# fpga-enet2.net
KiCad netlist of a schematic drawn in Altium Designer
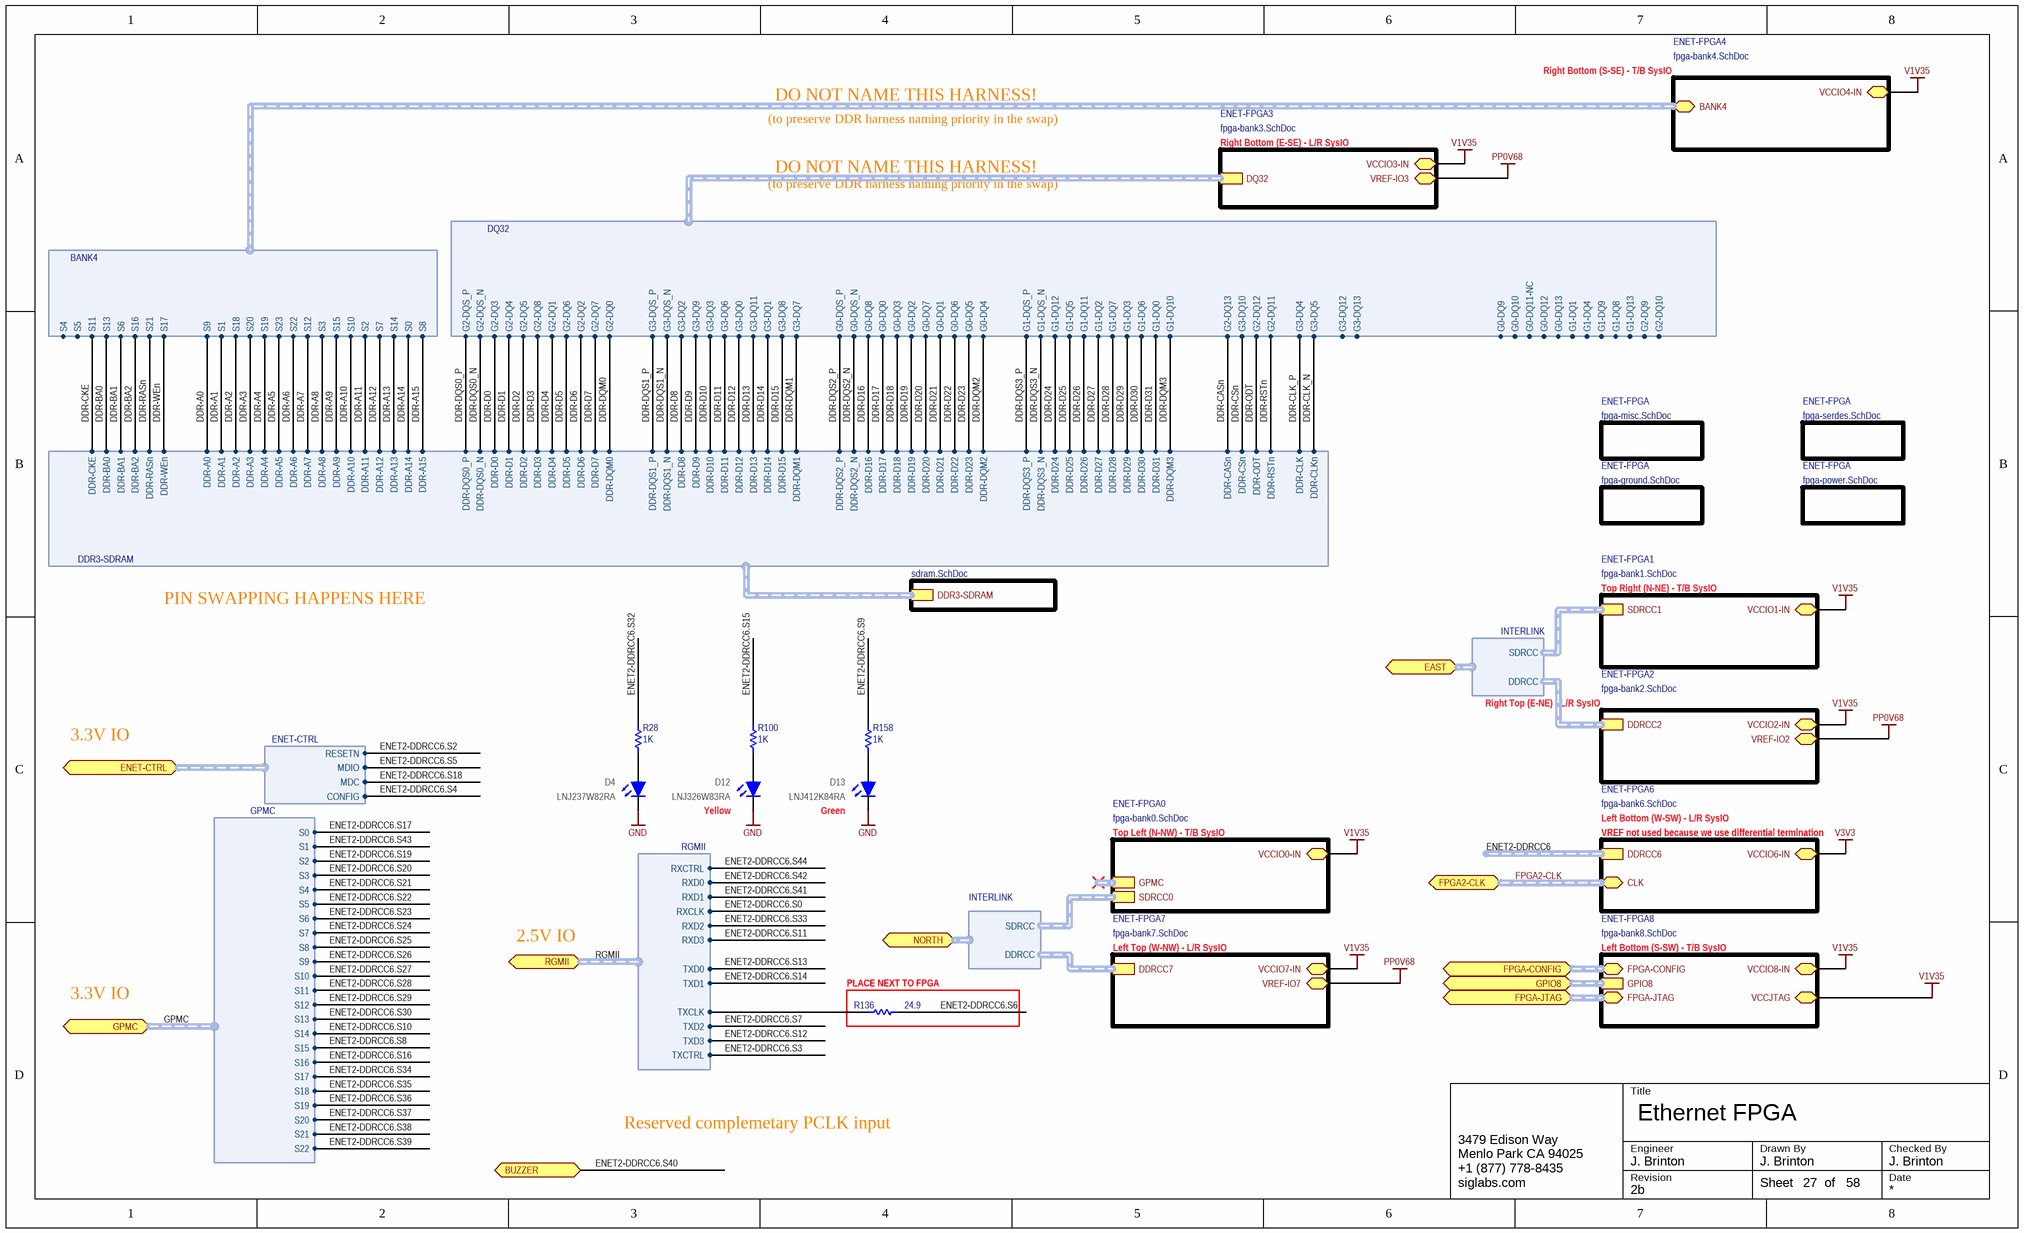
[diagram p0: fpga-enet2.SchDoc]

(export (version "E")
  (design (tool "Eeschema 10.0.6"))
  (components
    (comp (ref "D4")
      (value "LNJ237W82RA")
      (footprint "0603_LED")
      (description "LED, SMT 0603, Color Red, 5mA, 1.85V")
      (fields (field (name "MANUFACTURER") "Panasonic"))
      (libsource (lib "generic") (part "LED0603RD"))
    )
    (comp (ref "D12")
      (value "LNJ326W83RA")
      (footprint "0603_LED")
      (description "LED, SMT 0603, Color Green, 10mA, 2.05V")
      (fields (field (name "MANUFACTURER") "Panasonic"))
      (libsource (lib "generic") (part "LED0603GR"))
    )
    (comp (ref "D13")
      (value "LNJ412K84RA")
      (footprint "0603_LED")
      (description "LED, SMT 0603, Color Yellow, 10mA, 2.05V")
      (fields (field (name "MANUFACTURER") "Panasonic"))
      (libsource (lib "generic") (part "LED0603Y"))
    )
    (comp (ref "R28")
      (value "1K")
      (footprint "generic:0402")
      (description "Thick Film Resistor 1k ±1% 0402")
      (fields (field (name "MANUFACTURER") "Yageo") (field (name "TOLERANCE") "±1%"))
      (libsource (lib "Graviton") (part "RES 0402"))
    )
    (comp (ref "R100")
      (value "1K")
      (footprint "generic:0402")
      (description "Thick Film Resistor 1k ±1% 0402")
      (fields (field (name "MANUFACTURER") "Yageo") (field (name "TOLERANCE") "±1%"))
      (libsource (lib "Graviton") (part "RES 0402"))
    )
    (comp (ref "R136")
      (value "24.9")
      (footprint "generic:0603")
      (description "Thick Film Resistor 24.9 ±1% 0603")
      (fields (field (name "MANUFACTURER") "Panasonic") (field (name "TOLERANCE") "±1%"))
      (libsource (lib "Graviton") (part "RES 0603"))
    )
    (comp (ref "R158")
      (value "1K")
      (footprint "generic:0402")
      (description "Thick Film Resistor 1k ±1% 0402")
      (fields (field (name "MANUFACTURER") "Yageo") (field (name "TOLERANCE") "±1%"))
      (libsource (lib "Graviton") (part "RES 0402"))
    )
  )
  (nets
    (net (code "93") (name "/ENET2-DDRCC6.S6") (class "Default")
      (node (ref "R136") (pin "2") (pinfunction "2_2") (pintype "passive"))
    )
    (net (code "96") (name "/ENET2-DDRCC6.S9") (class "Default")
      (node (ref "R158") (pin "2") (pinfunction "2_2") (pintype "passive"))
    )
    (net (code "102") (name "/ENET2-DDRCC6.S15") (class "Default")
      (node (ref "R100") (pin "2") (pinfunction "2_2") (pintype "passive"))
    )
    (net (code "118") (name "/ENET2-DDRCC6.S32") (class "Default")
      (node (ref "R28") (pin "2") (pinfunction "2_2") (pintype "passive"))
    )
    (net (code "139") (name "/TXCLK") (class "Default")
      (node (ref "R136") (pin "1") (pinfunction "1_1") (pintype "passive"))
    )
    (net (code "147") (name "GND") (class "Default")
      (node (ref "D12") (pin "2") (pinfunction "K_2") (pintype "passive"))
      (node (ref "D13") (pin "2") (pinfunction "K_2") (pintype "passive"))
      (node (ref "D4") (pin "2") (pinfunction "K_2") (pintype "passive"))
    )
    (net (code "148") (name "Net-(D4-A)") (class "Default")
      (node (ref "D4") (pin "1") (pinfunction "A_1") (pintype "passive"))
      (node (ref "R28") (pin "1") (pinfunction "1_1") (pintype "passive"))
    )
    (net (code "149") (name "Net-(D12-A)") (class "Default")
      (node (ref "D12") (pin "1") (pinfunction "A_1") (pintype "passive"))
      (node (ref "R100") (pin "1") (pinfunction "1_1") (pintype "passive"))
    )
    (net (code "150") (name "Net-(D13-A)") (class "Default")
      (node (ref "D13") (pin "1") (pinfunction "A_1") (pintype "passive"))
      (node (ref "R158") (pin "1") (pinfunction "1_1") (pintype "passive"))
    )
  )
)
